# 10-DPLL-1.net
KiCad netlist of a schematic drawn in Altium Designer
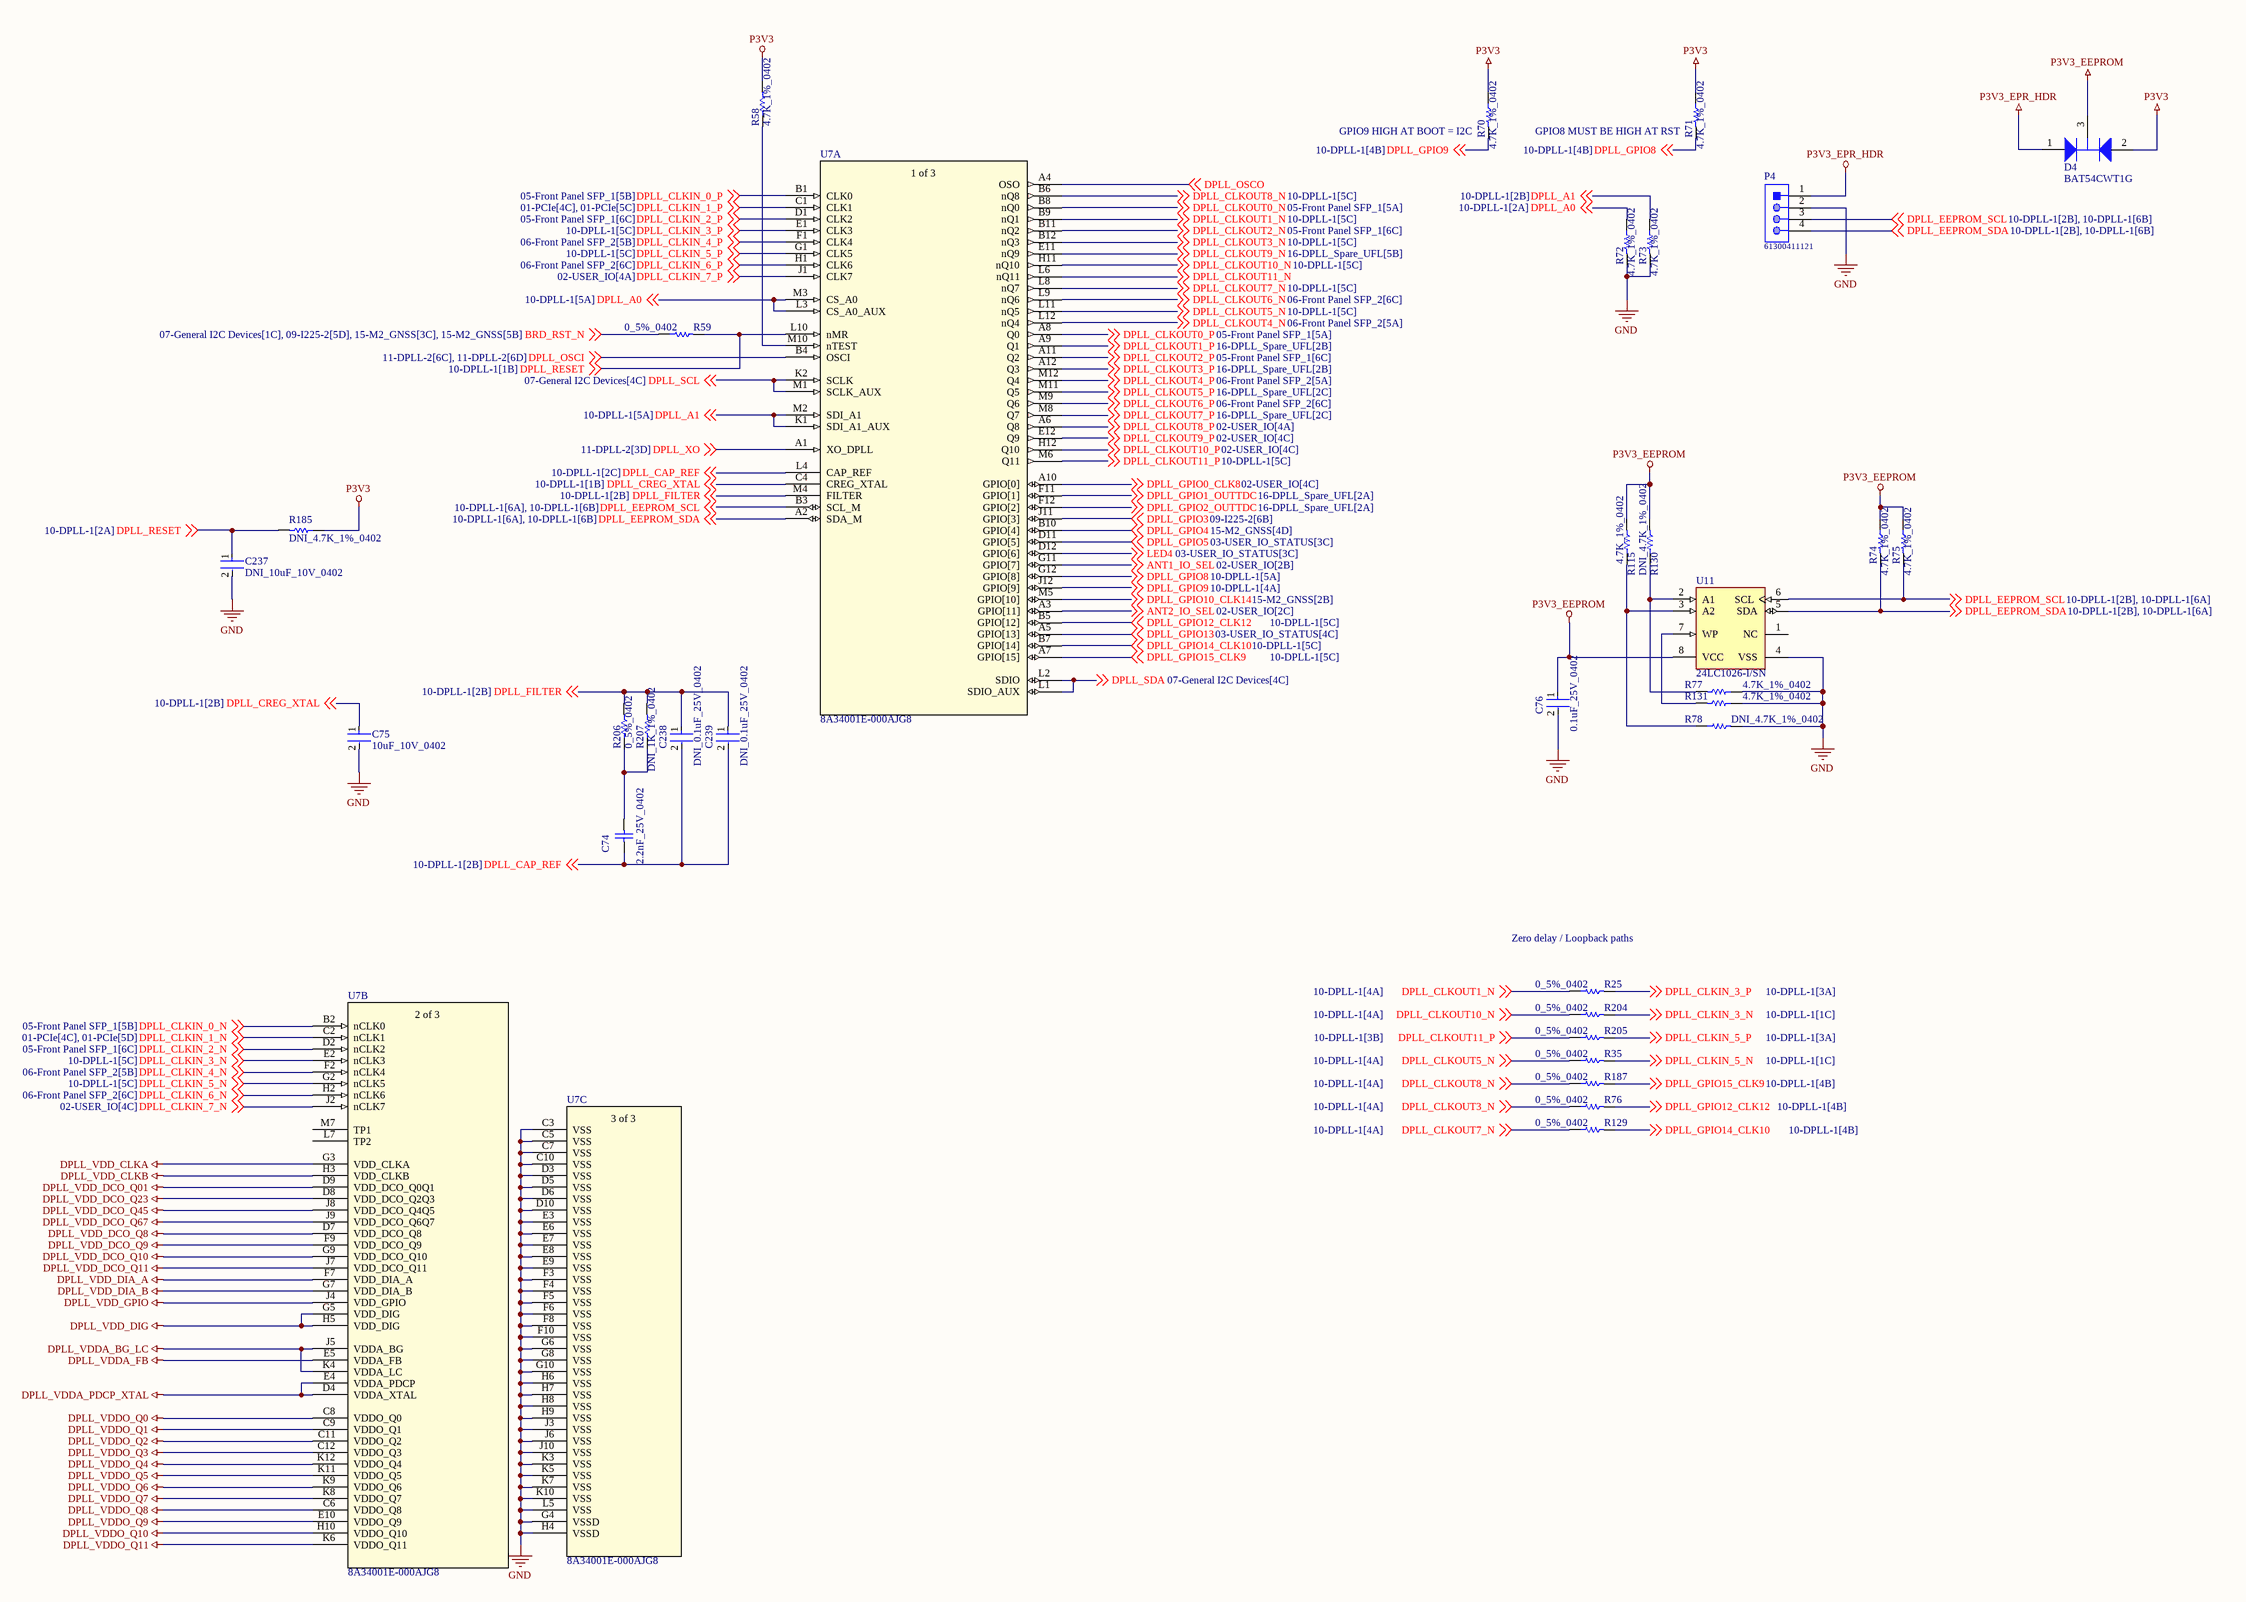
[diagram p0: 10-DPLL-1.SchDoc]

(export (version "E")
  (design (tool "Eeschema 10.0.6"))
  (components
    (comp (ref "C74")
      (value "2.2nF_25V_0402")
      (footprint "CAPC1005X56X25LL10T15")
      (fields
        (field (name "MANUFACTURER") "AVX Interconnect / Elco")
        (field (name "PART NUMBER") "04025C222JAT2A")
      )
      (libsource (lib "Altium Content Vault") (part "CAP"))
    )
    (comp (ref "C75")
      (value "10uF_10V_0402")
      (footprint "FP-CL05A106MP5NUNC-MFG")
      (description "CAP CER 10UF 10V X5R 0402")
      (fields
        (field (name "OCTOPART") "https://octopart.com/cl05a106mp5nunc-samsung-22457395")
        (field (name "TOLERANCE") "20%")
      )
      (libsource (lib "Altium Content Vault") (part "b4654b650e69147ec39a6b967a45e02"))
    )
    (comp (ref "C76")
      (value "0.1uF_25V_0402")
      (footprint "FP-0402-L_1_0_1-W_0_5_0_1-IPC_C")
      (description "General Purpose Ceramic Capacitor, 0402, 100nF, 10%, X7R, 15%, 25V")
      (fields (field (name "VOLTAGE") "25V") (field (name "TOLERANCE") "10%"))
      (libsource (lib "Altium Content Vault") (part "b4654b650e69147ec39a6b967a45e02"))
    )
    (comp (ref "C237")
      (value "DNI_10uF_10V_0402")
      (footprint "FP-CL05A106MP5NUNC-MFG")
      (description "CAP CER 10UF 10V X5R 0402")
      (fields
        (field (name "OCTOPART") "https://octopart.com/cl05a106mp5nunc-samsung-22457395")
        (field (name "TOLERANCE") "20%")
      )
      (libsource (lib "Altium Content Vault") (part "b4654b650e69147ec39a6b967a45e02"))
    )
    (comp (ref "C238")
      (value "DNI_0.1uF_25V_0402")
      (footprint "FP-0402-L_1_0_1-W_0_5_0_1-IPC_C")
      (description "General Purpose Ceramic Capacitor, 0402, 100nF, 10%, X7R, 15%, 25V")
      (fields (field (name "VOLTAGE") "25V") (field (name "TOLERANCE") "10%"))
      (libsource (lib "Altium Content Vault") (part "b4654b650e69147ec39a6b967a45e02"))
    )
    (comp (ref "C239")
      (value "DNI_0.1uF_25V_0402")
      (footprint "FP-0402-L_1_0_1-W_0_5_0_1-IPC_C")
      (description "General Purpose Ceramic Capacitor, 0402, 100nF, 10%, X7R, 15%, 25V")
      (fields (field (name "VOLTAGE") "25V") (field (name "TOLERANCE") "10%"))
      (libsource (lib "Altium Content Vault") (part "b4654b650e69147ec39a6b967a45e02"))
    )
    (comp (ref "D4")
      (value "BAT54CWT1G")
      (footprint "ONSC-SOT-323-3-419-04_V")
      (description "Dual Series Cathode Schottky Barrier Diodes, 3-Pin SOT-323, Pb-Free, Tape and Reel")
      (fields (field (name "MANUFACTURER") "On Semiconductor"))
      (libsource (lib "Altium Content Vault") (part "ONSC-D-A1A2K3-3"))
    )
    (comp (ref "P4")
      (value "61300411121")
      (footprint "61300411121")
      (description "THT Vertical Pin Header WR-PHD, Pitch 2.54 mm, Single Row, 4 pins")
      (fields (field (name "MANUFACTURER") "Wurth Elektronik") (field (name "PUBLISHER") "WurthElektronik"))
      (libsource (lib "Altium Content Vault") (part "WE-CN-1P-M-R4"))
    )
    (comp (ref "R25")
      (value "0_5%_0402")
      (footprint "RESC1005X40X25LL10T10")
      (fields (field (name "MANUFACTURER") "KOA Speer") (field (name "PART NUMBER") "RK73Z1ETTP"))
      (libsource (lib "Altium Content Vault") (part "RES"))
    )
    (comp (ref "R35")
      (value "0_5%_0402")
      (footprint "RESC1005X40X25LL10T10")
      (fields (field (name "MANUFACTURER") "KOA Speer") (field (name "PART NUMBER") "RK73Z1ETTP"))
      (libsource (lib "Altium Content Vault") (part "RES"))
    )
    (comp (ref "R58")
      (value "4.7K_1%_0402")
      (footprint "RESC1005X40X25NL10T10")
      (fields (field (name "MANUFACTURER") "Bourns") (field (name "PART NUMBER") "CR0402-FX-4701GLF"))
      (libsource (lib "Altium Content Vault") (part "RES"))
    )
    (comp (ref "R59")
      (value "0_5%_0402")
      (footprint "RESC1005X40X25LL10T10")
      (fields (field (name "MANUFACTURER") "KOA Speer") (field (name "PART NUMBER") "RK73Z1ETTP"))
      (libsource (lib "Altium Content Vault") (part "RES"))
    )
    (comp (ref "R70")
      (value "4.7K_1%_0402")
      (footprint "RESC1005X40X25NL10T10")
      (fields (field (name "MANUFACTURER") "Bourns") (field (name "PART NUMBER") "CR0402-FX-4701GLF"))
      (libsource (lib "Altium Content Vault") (part "RES"))
    )
    (comp (ref "R71")
      (value "4.7K_1%_0402")
      (footprint "RESC1005X40X25NL10T10")
      (fields (field (name "MANUFACTURER") "Bourns") (field (name "PART NUMBER") "CR0402-FX-4701GLF"))
      (libsource (lib "Altium Content Vault") (part "RES"))
    )
    (comp (ref "R72")
      (value "4.7K_1%_0402")
      (footprint "RESC1005X40X25NL10T10")
      (fields (field (name "MANUFACTURER") "Bourns") (field (name "PART NUMBER") "CR0402-FX-4701GLF"))
      (libsource (lib "Altium Content Vault") (part "RES"))
    )
    (comp (ref "R73")
      (value "4.7K_1%_0402")
      (footprint "RESC1005X40X25NL10T10")
      (fields (field (name "MANUFACTURER") "Bourns") (field (name "PART NUMBER") "CR0402-FX-4701GLF"))
      (libsource (lib "Altium Content Vault") (part "RES"))
    )
    (comp (ref "R74")
      (value "4.7K_1%_0402")
      (footprint "RESC1005X40X25NL10T10")
      (fields (field (name "MANUFACTURER") "Bourns") (field (name "PART NUMBER") "CR0402-FX-4701GLF"))
      (libsource (lib "Altium Content Vault") (part "RES"))
    )
    (comp (ref "R75")
      (value "4.7K_1%_0402")
      (footprint "RESC1005X40X25NL10T10")
      (fields (field (name "MANUFACTURER") "Bourns") (field (name "PART NUMBER") "CR0402-FX-4701GLF"))
      (libsource (lib "Altium Content Vault") (part "RES"))
    )
    (comp (ref "R76")
      (value "0_5%_0402")
      (footprint "RESC1005X40X25LL10T10")
      (fields (field (name "MANUFACTURER") "KOA Speer") (field (name "PART NUMBER") "RK73Z1ETTP"))
      (libsource (lib "Altium Content Vault") (part "RES"))
    )
    (comp (ref "R77")
      (value "4.7K_1%_0402")
      (footprint "RESC1005X40X25NL10T10")
      (fields (field (name "MANUFACTURER") "Bourns") (field (name "PART NUMBER") "CR0402-FX-4701GLF"))
      (libsource (lib "Altium Content Vault") (part "RES"))
    )
    (comp (ref "R78")
      (value "DNI_4.7K_1%_0402")
      (footprint "RESC1005X40X25NL10T10")
      (fields (field (name "MANUFACTURER") "Bourns") (field (name "PART NUMBER") "CR0402-FX-4701GLF"))
      (libsource (lib "Altium Content Vault") (part "RES"))
    )
    (comp (ref "R115")
      (value "4.7K_1%_0402")
      (footprint "RESC1005X40X25NL10T10")
      (fields (field (name "MANUFACTURER") "Bourns") (field (name "PART NUMBER") "CR0402-FX-4701GLF"))
      (libsource (lib "Altium Content Vault") (part "RES"))
    )
    (comp (ref "R129")
      (value "0_5%_0402")
      (footprint "RESC1005X40X25LL10T10")
      (fields (field (name "MANUFACTURER") "KOA Speer") (field (name "PART NUMBER") "RK73Z1ETTP"))
      (libsource (lib "Altium Content Vault") (part "RES"))
    )
    (comp (ref "R130")
      (value "DNI_4.7K_1%_0402")
      (footprint "RESC1005X40X25NL10T10")
      (fields (field (name "MANUFACTURER") "Bourns") (field (name "PART NUMBER") "CR0402-FX-4701GLF"))
      (libsource (lib "Altium Content Vault") (part "RES"))
    )
    (comp (ref "R131")
      (value "4.7K_1%_0402")
      (footprint "RESC1005X40X25NL10T10")
      (fields (field (name "MANUFACTURER") "Bourns") (field (name "PART NUMBER") "CR0402-FX-4701GLF"))
      (libsource (lib "Altium Content Vault") (part "RES"))
    )
    (comp (ref "R185")
      (value "DNI_4.7K_1%_0402")
      (footprint "RESC1005X40X25NL10T10")
      (fields (field (name "MANUFACTURER") "Bourns") (field (name "PART NUMBER") "CR0402-FX-4701GLF"))
      (libsource (lib "Altium Content Vault") (part "RES"))
    )
    (comp (ref "R187")
      (value "0_5%_0402")
      (footprint "RESC1005X40X25LL10T10")
      (fields (field (name "MANUFACTURER") "KOA Speer") (field (name "PART NUMBER") "RK73Z1ETTP"))
      (libsource (lib "Altium Content Vault") (part "RES"))
    )
    (comp (ref "R204")
      (value "0_5%_0402")
      (footprint "RESC1005X40X25LL10T10")
      (fields (field (name "MANUFACTURER") "KOA Speer") (field (name "PART NUMBER") "RK73Z1ETTP"))
      (libsource (lib "Altium Content Vault") (part "RES"))
    )
    (comp (ref "R205")
      (value "0_5%_0402")
      (footprint "RESC1005X40X25LL10T10")
      (fields (field (name "MANUFACTURER") "KOA Speer") (field (name "PART NUMBER") "RK73Z1ETTP"))
      (libsource (lib "Altium Content Vault") (part "RES"))
    )
    (comp (ref "R206")
      (value "0_5%_0402")
      (footprint "RESC1005X40X25LL10T10")
      (fields (field (name "MANUFACTURER") "KOA Speer") (field (name "PART NUMBER") "RK73Z1ETTP"))
      (libsource (lib "Altium Content Vault") (part "RES"))
    )
    (comp (ref "R207")
      (value "DNI_1K_1%_0402")
      (footprint "RESC1005X40X25NL05T05")
      (fields (field (name "MANUFACTURER") "Vishay Dale") (field (name "PART NUMBER") "CRCW04021K00FKTD"))
      (libsource (lib "Altium Content Vault") (part "RES"))
    )
    (comp (ref "U7")
      (value "8A34001E-000AJG8")
      (footprint "144-CABGA_REN")
      (description "No Description Available")
      (fields (field (name "COPYRIGHT") "Copyright (C) 2024 Ultra Librarian. All rights reserved."))
      (libsource (lib "8A34001E-000AJG8") (part "8A34001E-000AJG8"))
    )
    (comp (ref "U11")
      (value "24LC1026-I/SN")
      (footprint "MCHP-SOIC-SN8_N")
      (description "1024K bits I2C™ Serial EEPROM, 2.5 to 5.5 V, 400 kHz, -40 to 85 degC, 8-pin SOIC (SN8), Tube")
      (fields (field (name "MANUFACTURER") "Microchip"))
      (libsource (lib "Altium Content Vault") (part "MCHP-24LC1026-SOIC-8"))
    )
  )
  (nets
    (net (code "1") (name "ANT1_IO_SEL") (class "Default")
      (node (ref "U7") (pin "G11") (pinfunction "GPIO[7]_G11") (pintype "bidirectional"))
    )
    (net (code "2") (name "ANT2_IO_SEL") (class "Default")
      (node (ref "U7") (pin "A3") (pinfunction "GPIO[11]_A3") (pintype "bidirectional"))
    )
    (net (code "3") (name "BRD_RST_N") (class "Default")
      (node (ref "R59") (pin "1") (pinfunction "1_1") (pintype "passive"))
    )
    (net (code "4") (name "DPLL_A0") (class "Default")
      (node (ref "R72") (pin "1") (pinfunction "1_1") (pintype "passive"))
      (node (ref "U7") (pin "L3") (pinfunction "CS_A0_AUX_L3") (pintype "input"))
      (node (ref "U7") (pin "M3") (pinfunction "CS_A0_M3") (pintype "input"))
    )
    (net (code "5") (name "DPLL_A1") (class "Default")
      (node (ref "R73") (pin "1") (pinfunction "1_1") (pintype "passive"))
      (node (ref "U7") (pin "K1") (pinfunction "SDI_A1_AUX_K1") (pintype "input"))
      (node (ref "U7") (pin "M2") (pinfunction "SDI_A1_M2") (pintype "input"))
    )
    (net (code "6") (name "DPLL_CAP_REF") (class "Default")
      (node (ref "C238") (pin "2") (pinfunction "2_2") (pintype "passive"))
      (node (ref "C239") (pin "2") (pinfunction "2_2") (pintype "passive"))
      (node (ref "C74") (pin "1") (pinfunction "1_1") (pintype "passive"))
      (node (ref "U7") (pin "L4") (pinfunction "CAP_REF_L4") (pintype "passive"))
    )
    (net (code "7") (name "DPLL_CLKIN_0_N") (class "Default")
      (node (ref "U7") (pin "B2") (pinfunction "nCLK0_B2") (pintype "input"))
    )
    (net (code "8") (name "DPLL_CLKIN_0_P") (class "Default")
      (node (ref "U7") (pin "B1") (pinfunction "CLK0_B1") (pintype "input"))
    )
    (net (code "9") (name "DPLL_CLKIN_1_N") (class "Default")
      (node (ref "U7") (pin "C2") (pinfunction "nCLK1_C2") (pintype "input"))
    )
    (net (code "10") (name "DPLL_CLKIN_1_P") (class "Default")
      (node (ref "U7") (pin "C1") (pinfunction "CLK1_C1") (pintype "input"))
    )
    (net (code "11") (name "DPLL_CLKIN_2_N") (class "Default")
      (node (ref "U7") (pin "D2") (pinfunction "nCLK2_D2") (pintype "input"))
    )
    (net (code "12") (name "DPLL_CLKIN_2_P") (class "Default")
      (node (ref "U7") (pin "D1") (pinfunction "CLK2_D1") (pintype "input"))
    )
    (net (code "13") (name "DPLL_CLKIN_3_N") (class "Default")
      (node (ref "R204") (pin "2") (pinfunction "2_2") (pintype "passive"))
      (node (ref "U7") (pin "E2") (pinfunction "nCLK3_E2") (pintype "input"))
    )
    (net (code "14") (name "DPLL_CLKIN_3_P") (class "Default")
      (node (ref "R25") (pin "2") (pinfunction "2_2") (pintype "passive"))
      (node (ref "U7") (pin "E1") (pinfunction "CLK3_E1") (pintype "input"))
    )
    (net (code "15") (name "DPLL_CLKIN_4_N") (class "Default")
      (node (ref "U7") (pin "F2") (pinfunction "nCLK4_F2") (pintype "input"))
    )
    (net (code "16") (name "DPLL_CLKIN_4_P") (class "Default")
      (node (ref "U7") (pin "F1") (pinfunction "CLK4_F1") (pintype "input"))
    )
    (net (code "17") (name "DPLL_CLKIN_5_N") (class "Default")
      (node (ref "R35") (pin "2") (pinfunction "2_2") (pintype "passive"))
      (node (ref "U7") (pin "G2") (pinfunction "nCLK5_G2") (pintype "input"))
    )
    (net (code "18") (name "DPLL_CLKIN_5_P") (class "Default")
      (node (ref "R205") (pin "2") (pinfunction "2_2") (pintype "passive"))
      (node (ref "U7") (pin "G1") (pinfunction "CLK5_G1") (pintype "input"))
    )
    (net (code "19") (name "DPLL_CLKIN_6_N") (class "Default")
      (node (ref "U7") (pin "H2") (pinfunction "nCLK6_H2") (pintype "input"))
    )
    (net (code "20") (name "DPLL_CLKIN_6_P") (class "Default")
      (node (ref "U7") (pin "H1") (pinfunction "CLK6_H1") (pintype "input"))
    )
    (net (code "21") (name "DPLL_CLKIN_7_N") (class "Default")
      (node (ref "U7") (pin "J2") (pinfunction "nCLK7_J2") (pintype "input"))
    )
    (net (code "22") (name "DPLL_CLKIN_7_P") (class "Default")
      (node (ref "U7") (pin "J1") (pinfunction "CLK7_J1") (pintype "input"))
    )
    (net (code "23") (name "DPLL_CLKOUT0_N") (class "Default")
      (node (ref "U7") (pin "B8") (pinfunction "nQ0_B8") (pintype "output"))
    )
    (net (code "24") (name "DPLL_CLKOUT0_P") (class "Default")
      (node (ref "U7") (pin "A8") (pinfunction "Q0_A8") (pintype "output"))
    )
    (net (code "25") (name "DPLL_CLKOUT1_N") (class "Default")
      (node (ref "R25") (pin "1") (pinfunction "1_1") (pintype "passive"))
      (node (ref "U7") (pin "B9") (pinfunction "nQ1_B9") (pintype "output"))
    )
    (net (code "26") (name "DPLL_CLKOUT1_P") (class "Default")
      (node (ref "U7") (pin "A9") (pinfunction "Q1_A9") (pintype "output"))
    )
    (net (code "27") (name "DPLL_CLKOUT2_N") (class "Default")
      (node (ref "U7") (pin "B11") (pinfunction "nQ2_B11") (pintype "output"))
    )
    (net (code "28") (name "DPLL_CLKOUT2_P") (class "Default")
      (node (ref "U7") (pin "A11") (pinfunction "Q2_A11") (pintype "output"))
    )
    (net (code "29") (name "DPLL_CLKOUT3_N") (class "Default")
      (node (ref "R76") (pin "1") (pinfunction "1_1") (pintype "passive"))
      (node (ref "U7") (pin "B12") (pinfunction "nQ3_B12") (pintype "output"))
    )
    (net (code "30") (name "DPLL_CLKOUT3_P") (class "Default")
      (node (ref "U7") (pin "A12") (pinfunction "Q3_A12") (pintype "output"))
    )
    (net (code "31") (name "DPLL_CLKOUT4_N") (class "Default")
      (node (ref "U7") (pin "L12") (pinfunction "nQ4_L12") (pintype "output"))
    )
    (net (code "32") (name "DPLL_CLKOUT4_P") (class "Default")
      (node (ref "U7") (pin "M12") (pinfunction "Q4_M12") (pintype "output"))
    )
    (net (code "33") (name "DPLL_CLKOUT5_N") (class "Default")
      (node (ref "R35") (pin "1") (pinfunction "1_1") (pintype "passive"))
      (node (ref "U7") (pin "L11") (pinfunction "nQ5_L11") (pintype "output"))
    )
    (net (code "34") (name "DPLL_CLKOUT5_P") (class "Default")
      (node (ref "U7") (pin "M11") (pinfunction "Q5_M11") (pintype "output"))
    )
    (net (code "35") (name "DPLL_CLKOUT6_N") (class "Default")
      (node (ref "U7") (pin "L9") (pinfunction "nQ6_L9") (pintype "output"))
    )
    (net (code "36") (name "DPLL_CLKOUT6_P") (class "Default")
      (node (ref "U7") (pin "M9") (pinfunction "Q6_M9") (pintype "output"))
    )
    (net (code "37") (name "DPLL_CLKOUT7_N") (class "Default")
      (node (ref "R129") (pin "1") (pinfunction "1_1") (pintype "passive"))
      (node (ref "U7") (pin "L8") (pinfunction "nQ7_L8") (pintype "output"))
    )
    (net (code "38") (name "DPLL_CLKOUT7_P") (class "Default")
      (node (ref "U7") (pin "M8") (pinfunction "Q7_M8") (pintype "output"))
    )
    (net (code "39") (name "DPLL_CLKOUT8_N") (class "Default")
      (node (ref "R187") (pin "1") (pinfunction "1_1") (pintype "passive"))
      (node (ref "U7") (pin "B6") (pinfunction "nQ8_B6") (pintype "output"))
    )
    (net (code "40") (name "DPLL_CLKOUT8_P") (class "Default")
      (node (ref "U7") (pin "A6") (pinfunction "Q8_A6") (pintype "output"))
    )
    (net (code "41") (name "DPLL_CLKOUT9_N") (class "Default")
      (node (ref "U7") (pin "E11") (pinfunction "nQ9_E11") (pintype "output"))
    )
    (net (code "42") (name "DPLL_CLKOUT9_P") (class "Default")
      (node (ref "U7") (pin "E12") (pinfunction "Q9_E12") (pintype "output"))
    )
    (net (code "43") (name "DPLL_CLKOUT10_N") (class "Default")
      (node (ref "R204") (pin "1") (pinfunction "1_1") (pintype "passive"))
      (node (ref "U7") (pin "H11") (pinfunction "nQ10_H11") (pintype "output"))
    )
    (net (code "44") (name "DPLL_CLKOUT10_P") (class "Default")
      (node (ref "U7") (pin "H12") (pinfunction "Q10_H12") (pintype "output"))
    )
    (net (code "45") (name "DPLL_CLKOUT11_N") (class "Default")
      (node (ref "U7") (pin "L6") (pinfunction "nQ11_L6") (pintype "output"))
    )
    (net (code "46") (name "DPLL_CLKOUT11_P") (class "Default")
      (node (ref "R205") (pin "1") (pinfunction "1_1") (pintype "passive"))
      (node (ref "U7") (pin "M6") (pinfunction "Q11_M6") (pintype "output"))
    )
    (net (code "47") (name "DPLL_CREG_XTAL") (class "Default")
      (node (ref "C75") (pin "1") (pinfunction "1_1") (pintype "passive"))
      (node (ref "U7") (pin "C4") (pinfunction "CREG_XTAL_C4") (pintype "passive"))
    )
    (net (code "48") (name "DPLL_EEPROM_SCL") (class "Default")
      (node (ref "P4") (pin "3") (pinfunction "3_3") (pintype "passive"))
      (node (ref "R75") (pin "2") (pinfunction "2_2") (pintype "passive"))
      (node (ref "U11") (pin "6") (pinfunction "SCL_6") (pintype "input"))
      (node (ref "U7") (pin "B3") (pinfunction "SCL_M_B3") (pintype "bidirectional"))
    )
    (net (code "49") (name "DPLL_EEPROM_SDA") (class "Default")
      (node (ref "P4") (pin "4") (pinfunction "4_4") (pintype "passive"))
      (node (ref "R74") (pin "2") (pinfunction "2_2") (pintype "passive"))
      (node (ref "U11") (pin "5") (pinfunction "SDA_5") (pintype "bidirectional"))
      (node (ref "U7") (pin "A2") (pinfunction "SDA_M_A2") (pintype "bidirectional"))
    )
    (net (code "50") (name "DPLL_FILTER") (class "Default")
      (node (ref "C238") (pin "1") (pinfunction "1_1") (pintype "passive"))
      (node (ref "C239") (pin "1") (pinfunction "1_1") (pintype "passive"))
      (node (ref "R206") (pin "2") (pinfunction "2_2") (pintype "passive"))
      (node (ref "R207") (pin "2") (pinfunction "2_2") (pintype "passive"))
      (node (ref "U7") (pin "M4") (pinfunction "FILTER_M4") (pintype "passive"))
    )
    (net (code "51") (name "DPLL_GPIO0_CLK8") (class "Default")
      (node (ref "U7") (pin "A10") (pinfunction "GPIO[0]_A10") (pintype "bidirectional"))
    )
    (net (code "52") (name "DPLL_GPIO1_OUTTDC") (class "Default")
      (node (ref "U7") (pin "F11") (pinfunction "GPIO[1]_F11") (pintype "bidirectional"))
    )
    (net (code "53") (name "DPLL_GPIO2_OUTTDC") (class "Default")
      (node (ref "U7") (pin "F12") (pinfunction "GPIO[2]_F12") (pintype "bidirectional"))
    )
    (net (code "54") (name "DPLL_GPIO3") (class "Default")
      (node (ref "U7") (pin "J11") (pinfunction "GPIO[3]_J11") (pintype "bidirectional"))
    )
    (net (code "55") (name "DPLL_GPIO4") (class "Default")
      (node (ref "U7") (pin "B10") (pinfunction "GPIO[4]_B10") (pintype "bidirectional"))
    )
    (net (code "56") (name "DPLL_GPIO5") (class "Default")
      (node (ref "U7") (pin "D11") (pinfunction "GPIO[5]_D11") (pintype "bidirectional"))
    )
    (net (code "57") (name "DPLL_GPIO8") (class "Default")
      (node (ref "R71") (pin "2") (pinfunction "2_2") (pintype "passive"))
      (node (ref "U7") (pin "G12") (pinfunction "GPIO[8]_G12") (pintype "bidirectional"))
    )
    (net (code "58") (name "DPLL_GPIO9") (class "Default")
      (node (ref "R70") (pin "2") (pinfunction "2_2") (pintype "passive"))
      (node (ref "U7") (pin "J12") (pinfunction "GPIO[9]_J12") (pintype "bidirectional"))
    )
    (net (code "59") (name "DPLL_GPIO10_CLK14") (class "Default")
      (node (ref "U7") (pin "M5") (pinfunction "GPIO[10]_M5") (pintype "bidirectional"))
    )
    (net (code "60") (name "DPLL_GPIO12_CLK12") (class "Default")
      (node (ref "R76") (pin "2") (pinfunction "2_2") (pintype "passive"))
      (node (ref "U7") (pin "B5") (pinfunction "GPIO[12]_B5") (pintype "bidirectional"))
    )
    (net (code "61") (name "DPLL_GPIO13") (class "Default")
      (node (ref "U7") (pin "A5") (pinfunction "GPIO[13]_A5") (pintype "bidirectional"))
    )
    (net (code "62") (name "DPLL_GPIO14_CLK10") (class "Default")
      (node (ref "R129") (pin "2") (pinfunction "2_2") (pintype "passive"))
      (node (ref "U7") (pin "B7") (pinfunction "GPIO[14]_B7") (pintype "bidirectional"))
    )
    (net (code "63") (name "DPLL_GPIO15_CLK9") (class "Default")
      (node (ref "R187") (pin "2") (pinfunction "2_2") (pintype "passive"))
      (node (ref "U7") (pin "A7") (pinfunction "GPIO[15]_A7") (pintype "bidirectional"))
    )
    (net (code "64") (name "DPLL_OSCI") (class "Default")
      (node (ref "U7") (pin "B4") (pinfunction "OSCI_B4") (pintype "input"))
    )
    (net (code "65") (name "DPLL_OSCO") (class "Default")
      (node (ref "U7") (pin "A4") (pinfunction "OSO_A4") (pintype "output"))
    )
    (net (code "66") (name "DPLL_RESET") (class "Default")
      (node (ref "C237") (pin "1") (pinfunction "1_1") (pintype "passive"))
      (node (ref "R185") (pin "2") (pinfunction "2_2") (pintype "passive"))
      (node (ref "R59") (pin "2") (pinfunction "2_2") (pintype "passive"))
      (node (ref "U7") (pin "L10") (pinfunction "nMR_L10") (pintype "input"))
    )
    (net (code "67") (name "DPLL_SCL") (class "Default")
      (node (ref "U7") (pin "K2") (pinfunction "SCLK_K2") (pintype "input"))
      (node (ref "U7") (pin "M1") (pinfunction "SCLK_AUX_M1") (pintype "input"))
    )
    (net (code "68") (name "DPLL_SDA") (class "Default")
      (node (ref "U7") (pin "L1") (pinfunction "SDIO_AUX_L1") (pintype "bidirectional"))
      (node (ref "U7") (pin "L2") (pinfunction "SDIO_L2") (pintype "bidirectional"))
    )
    (net (code "69") (name "DPLL_VDDA_BG_LC") (class "Default")
      (node (ref "U7") (pin "J5") (pinfunction "VDDA_BG_J5") (pintype "power_in"))
      (node (ref "U7") (pin "K4") (pinfunction "VDDA_LC_K4") (pintype "power_in"))
    )
    (net (code "70") (name "DPLL_VDDA_FB") (class "Default")
      (node (ref "U7") (pin "E5") (pinfunction "VDDA_FB_E5") (pintype "power_in"))
    )
    (net (code "71") (name "DPLL_VDDA_PDCP_XTAL") (class "Default")
      (node (ref "U7") (pin "D4") (pinfunction "VDDA_XTAL_D4") (pintype "power_in"))
      (node (ref "U7") (pin "E4") (pinfunction "VDDA_PDCP_E4") (pintype "power_in"))
    )
    (net (code "72") (name "DPLL_VDDO_Q0") (class "Default")
      (node (ref "U7") (pin "C8") (pinfunction "VDDO_Q0_C8") (pintype "power_in"))
    )
    (net (code "73") (name "DPLL_VDDO_Q1") (class "Default")
      (node (ref "U7") (pin "C9") (pinfunction "VDDO_Q1_C9") (pintype "power_in"))
    )
    (net (code "74") (name "DPLL_VDDO_Q2") (class "Default")
      (node (ref "U7") (pin "C11") (pinfunction "VDDO_Q2_C11") (pintype "power_in"))
    )
    (net (code "75") (name "DPLL_VDDO_Q3") (class "Default")
      (node (ref "U7") (pin "C12") (pinfunction "VDDO_Q3_C12") (pintype "power_in"))
    )
    (net (code "76") (name "DPLL_VDDO_Q4") (class "Default")
      (node (ref "U7") (pin "K12") (pinfunction "VDDO_Q4_K12") (pintype "power_in"))
    )
    (net (code "77") (name "DPLL_VDDO_Q5") (class "Default")
      (node (ref "U7") (pin "K11") (pinfunction "VDDO_Q5_K11") (pintype "power_in"))
    )
    (net (code "78") (name "DPLL_VDDO_Q6") (class "Default")
      (node (ref "U7") (pin "K9") (pinfunction "VDDO_Q6_K9") (pintype "power_in"))
    )
    (net (code "79") (name "DPLL_VDDO_Q7") (class "Default")
      (node (ref "U7") (pin "K8") (pinfunction "VDDO_Q7_K8") (pintype "power_in"))
    )
    (net (code "80") (name "DPLL_VDDO_Q8") (class "Default")
      (node (ref "U7") (pin "C6") (pinfunction "VDDO_Q8_C6") (pintype "power_in"))
    )
    (net (code "81") (name "DPLL_VDDO_Q9") (class "Default")
      (node (ref "U7") (pin "E10") (pinfunction "VDDO_Q9_E10") (pintype "power_in"))
    )
    (net (code "82") (name "DPLL_VDDO_Q10") (class "Default")
      (node (ref "U7") (pin "H10") (pinfunction "VDDO_Q10_H10") (pintype "power_in"))
    )
    (net (code "83") (name "DPLL_VDDO_Q11") (class "Default")
      (node (ref "U7") (pin "K6") (pinfunction "VDDO_Q11_K6") (pintype "power_in"))
    )
    (net (code "84") (name "DPLL_VDD_CLKA") (class "Default")
      (node (ref "U7") (pin "G3") (pinfunction "VDD_CLKA_G3") (pintype "power_in"))
    )
    (net (code "85") (name "DPLL_VDD_CLKB") (class "Default")
      (node (ref "U7") (pin "H3") (pinfunction "VDD_CLKB_H3") (pintype "power_in"))
    )
    (net (code "86") (name "DPLL_VDD_DCO_Q01") (class "Default")
      (node (ref "U7") (pin "D9") (pinfunction "VDD_DCO_Q0Q1_D9") (pintype "power_in"))
    )
    (net (code "87") (name "DPLL_VDD_DCO_Q8") (class "Default")
      (node (ref "U7") (pin "D7") (pinfunction "VDD_DCO_Q8_D7") (pintype "power_in"))
    )
    (net (code "88") (name "DPLL_VDD_DCO_Q9") (class "Default")
      (node (ref "U7") (pin "F9") (pinfunction "VDD_DCO_Q9_F9") (pintype "power_in"))
    )
    (net (code "89") (name "DPLL_VDD_DCO_Q10") (class "Default")
      (node (ref "U7") (pin "G9") (pinfunction "VDD_DCO_Q10_G9") (pintype "power_in"))
    )
    (net (code "90") (name "DPLL_VDD_DCO_Q11") (class "Default")
      (node (ref "U7") (pin "J7") (pinfunction "VDD_DCO_Q11_J7") (pintype "power_in"))
    )
    (net (code "91") (name "DPLL_VDD_DCO_Q23") (class "Default")
      (node (ref "U7") (pin "D8") (pinfunction "VDD_DCO_Q2Q3_D8") (pintype "power_in"))
    )
    (net (code "92") (name "DPLL_VDD_DCO_Q45") (class "Default")
      (node (ref "U7") (pin "J8") (pinfunction "VDD_DCO_Q4Q5_J8") (pintype "power_in"))
    )
    (net (code "93") (name "DPLL_VDD_DCO_Q67") (class "Default")
      (node (ref "U7") (pin "J9") (pinfunction "VDD_DCO_Q6Q7_J9") (pintype "power_in"))
    )
    (net (code "94") (name "DPLL_VDD_DIA_A") (class "Default")
      (node (ref "U7") (pin "F7") (pinfunction "VDD_DIA_A_F7") (pintype "power_in"))
    )
    (net (code "95") (name "DPLL_VDD_DIA_B") (class "Default")
      (node (ref "U7") (pin "G7") (pinfunction "VDD_DIA_B_G7") (pintype "power_in"))
    )
    (net (code "96") (name "DPLL_VDD_DIG") (class "Default")
      (node (ref "U7") (pin "G5") (pinfunction "VDD_DIG_G5") (pintype "power_in"))
      (node (ref "U7") (pin "H5") (pinfunction "VDD_DIG_H5") (pintype "power_in"))
    )
    (net (code "97") (name "DPLL_VDD_GPIO") (class "Default")
      (node (ref "U7") (pin "J4") (pinfunction "VDD_GPIO_J4") (pintype "power_in"))
    )
    (net (code "98") (name "DPLL_XO") (class "Default")
      (node (ref "U7") (pin "A1") (pinfunction "XO_DPLL_A1") (pintype "input"))
    )
    (net (code "99") (name "GND") (class "Default")
      (node (ref "C237") (pin "2") (pinfunction "2_2") (pintype "passive"))
      (node (ref "C75") (pin "2") (pinfunction "2_2") (pintype "passive"))
      (node (ref "C76") (pin "2") (pinfunction "2_2") (pintype "passive"))
      (node (ref "P4") (pin "2") (pinfunction "2_2") (pintype "passive"))
      (node (ref "R131") (pin "1") (pinfunction "1_1") (pintype "passive"))
      (node (ref "R72") (pin "2") (pinfunction "2_2") (pintype "passive"))
      (node (ref "R73") (pin "2") (pinfunction "2_2") (pintype "passive"))
      (node (ref "R77") (pin "1") (pinfunction "1_1") (pintype "passive"))
      (node (ref "R78") (pin "2") (pinfunction "2_2") (pintype "passive"))
      (node (ref "U11") (pin "4") (pinfunction "VSS_4") (pintype "power_in"))
      (node (ref "U7") (pin "C10") (pinfunction "VSS_C10") (pintype "power_in"))
      (node (ref "U7") (pin "C3") (pinfunction "VSS_C3") (pintype "power_in"))
      (node (ref "U7") (pin "C5") (pinfunction "VSS_C5") (pintype "power_in"))
      (node (ref "U7") (pin "C7") (pinfunction "VSS_C7") (pintype "power_in"))
      (node (ref "U7") (pin "D10") (pinfunction "VSS_D10") (pintype "power_in"))
      (node (ref "U7") (pin "D3") (pinfunction "VSS_D3") (pintype "power_in"))
      (node (ref "U7") (pin "D5") (pinfunction "VSS_D5") (pintype "power_in"))
      (node (ref "U7") (pin "D6") (pinfunction "VSS_D6") (pintype "power_in"))
      (node (ref "U7") (pin "E3") (pinfunction "VSS_E3") (pintype "power_in"))
      (node (ref "U7") (pin "E6") (pinfunction "VSS_E6") (pintype "power_in"))
      (node (ref "U7") (pin "E7") (pinfunction "VSS_E7") (pintype "power_in"))
      (node (ref "U7") (pin "E8") (pinfunction "VSS_E8") (pintype "power_in"))
      (node (ref "U7") (pin "E9") (pinfunction "VSS_E9") (pintype "power_in"))
      (node (ref "U7") (pin "F10") (pinfunction "VSS_F10") (pintype "power_in"))
      (node (ref "U7") (pin "F3") (pinfunction "VSS_F3") (pintype "power_in"))
      (node (ref "U7") (pin "F4") (pinfunction "VSS_F4") (pintype "power_in"))
      (node (ref "U7") (pin "F5") (pinfunction "VSS_F5") (pintype "power_in"))
      (node (ref "U7") (pin "F6") (pinfunction "VSS_F6") (pintype "power_in"))
      (node (ref "U7") (pin "F8") (pinfunction "VSS_F8") (pintype "power_in"))
      (node (ref "U7") (pin "G10") (pinfunction "VSS_G10") (pintype "power_in"))
      (node (ref "U7") (pin "G4") (pinfunction "VSSD_G4") (pintype "power_in"))
      (node (ref "U7") (pin "G6") (pinfunction "VSS_G6") (pintype "power_in"))
      (node (ref "U7") (pin "G8") (pinfunction "VSS_G8") (pintype "power_in"))
      (node (ref "U7") (pin "H4") (pinfunction "VSSD_H4") (pintype "power_in"))
      (node (ref "U7") (pin "H6") (pinfunction "VSS_H6") (pintype "power_in"))
      (node (ref "U7") (pin "H7") (pinfunction "VSS_H7") (pintype "power_in"))
      (node (ref "U7") (pin "H8") (pinfunction "VSS_H8") (pintype "power_in"))
      (node (ref "U7") (pin "H9") (pinfunction "VSS_H9") (pintype "power_in"))
      (node (ref "U7") (pin "J10") (pinfunction "VSS_J10") (pintype "power_in"))
      (node (ref "U7") (pin "J3") (pinfunction "VSS_J3") (pintype "power_in"))
      (node (ref "U7") (pin "J6") (pinfunction "VSS_J6") (pintype "power_in"))
      (node (ref "U7") (pin "K10") (pinfunction "VSS_K10") (pintype "power_in"))
      (node (ref "U7") (pin "K3") (pinfunction "VSS_K3") (pintype "power_in"))
      (node (ref "U7") (pin "K5") (pinfunction "VSS_K5") (pintype "power_in"))
      (node (ref "U7") (pin "K7") (pinfunction "VSS_K7") (pintype "power_in"))
      (node (ref "U7") (pin "L5") (pinfunction "VSS_L5") (pintype "power_in"))
    )
    (net (code "100") (name "LED4") (class "Default")
      (node (ref "U7") (pin "D12") (pinfunction "GPIO[6]_D12") (pintype "bidirectional"))
    )
    (net (code "101") (name "Net-(C74-Pad2)") (class "Default")
      (node (ref "C74") (pin "2") (pinfunction "2_2") (pintype "passive"))
      (node (ref "R206") (pin "1") (pinfunction "1_1") (pintype "passive"))
      (node (ref "R207") (pin "1") (pinfunction "1_1") (pintype "passive"))
    )
    (net (code "102") (name "Net-(U7A-nTEST)") (class "Default")
      (node (ref "R58") (pin "1") (pinfunction "1_1") (pintype "passive"))
      (node (ref "U7") (pin "M10") (pinfunction "nTEST_M10") (pintype "input"))
    )
    (net (code "103") (name "Net-(U11-A1)") (class "Default")
      (node (ref "R130") (pin "1") (pinfunction "1_1") (pintype "passive"))
      (node (ref "R77") (pin "2") (pinfunction "2_2") (pintype "passive"))
      (node (ref "U11") (pin "2") (pinfunction "A1_2") (pintype "input"))
    )
    (net (code "104") (name "Net-(U11-A2)") (class "Default")
      (node (ref "R115") (pin "1") (pinfunction "1_1") (pintype "passive"))
      (node (ref "R78") (pin "1") (pinfunction "1_1") (pintype "passive"))
      (node (ref "U11") (pin "3") (pinfunction "A2_3") (pintype "input"))
    )
    (net (code "105") (name "Net-(U11-WP)") (class "Default")
      (node (ref "R131") (pin "2") (pinfunction "2_2") (pintype "passive"))
      (node (ref "U11") (pin "7") (pinfunction "WP_7") (pintype "input"))
    )
    (net (code "106") (name "P3V3") (class "Default")
      (node (ref "D4") (pin "2") (pinfunction "A2_2") (pintype "passive"))
      (node (ref "R185") (pin "1") (pinfunction "1_1") (pintype "passive"))
      (node (ref "R58") (pin "2") (pinfunction "2_2") (pintype "passive"))
      (node (ref "R70") (pin "1") (pinfunction "1_1") (pintype "passive"))
      (node (ref "R71") (pin "1") (pinfunction "1_1") (pintype "passive"))
    )
    (net (code "107") (name "P3V3_EEPROM") (class "Default")
      (node (ref "C76") (pin "1") (pinfunction "1_1") (pintype "passive"))
      (node (ref "D4") (pin "3") (pinfunction "K_3") (pintype "passive"))
      (node (ref "R115") (pin "2") (pinfunction "2_2") (pintype "passive"))
      (node (ref "R130") (pin "2") (pinfunction "2_2") (pintype "passive"))
      (node (ref "R74") (pin "1") (pinfunction "1_1") (pintype "passive"))
      (node (ref "R75") (pin "1") (pinfunction "1_1") (pintype "passive"))
      (node (ref "U11") (pin "8") (pinfunction "VCC_8") (pintype "power_in"))
    )
    (net (code "108") (name "P3V3_EPR_HDR") (class "Default")
      (node (ref "D4") (pin "1") (pinfunction "A1_1") (pintype "passive"))
      (node (ref "P4") (pin "1") (pinfunction "1_1") (pintype "passive"))
    )
    (net (code "109") (name "unconnected-(U7B-TP1-PadM7)") (class "Default")
      (node (ref "U7") (pin "M7") (pinfunction "TP1_M7") (pintype "passive"))
    )
    (net (code "110") (name "unconnected-(U7B-TP2-PadL7)") (class "Default")
      (node (ref "U7") (pin "L7") (pinfunction "TP2_L7") (pintype "passive"))
    )
    (net (code "111") (name "unconnected-(U11-NC-Pad1)") (class "Default")
      (node (ref "U11") (pin "1") (pinfunction "NC_1") (pintype "passive"))
    )
  )
)
